# Main.net
KiCad netlist of a schematic drawn in Altium Designer
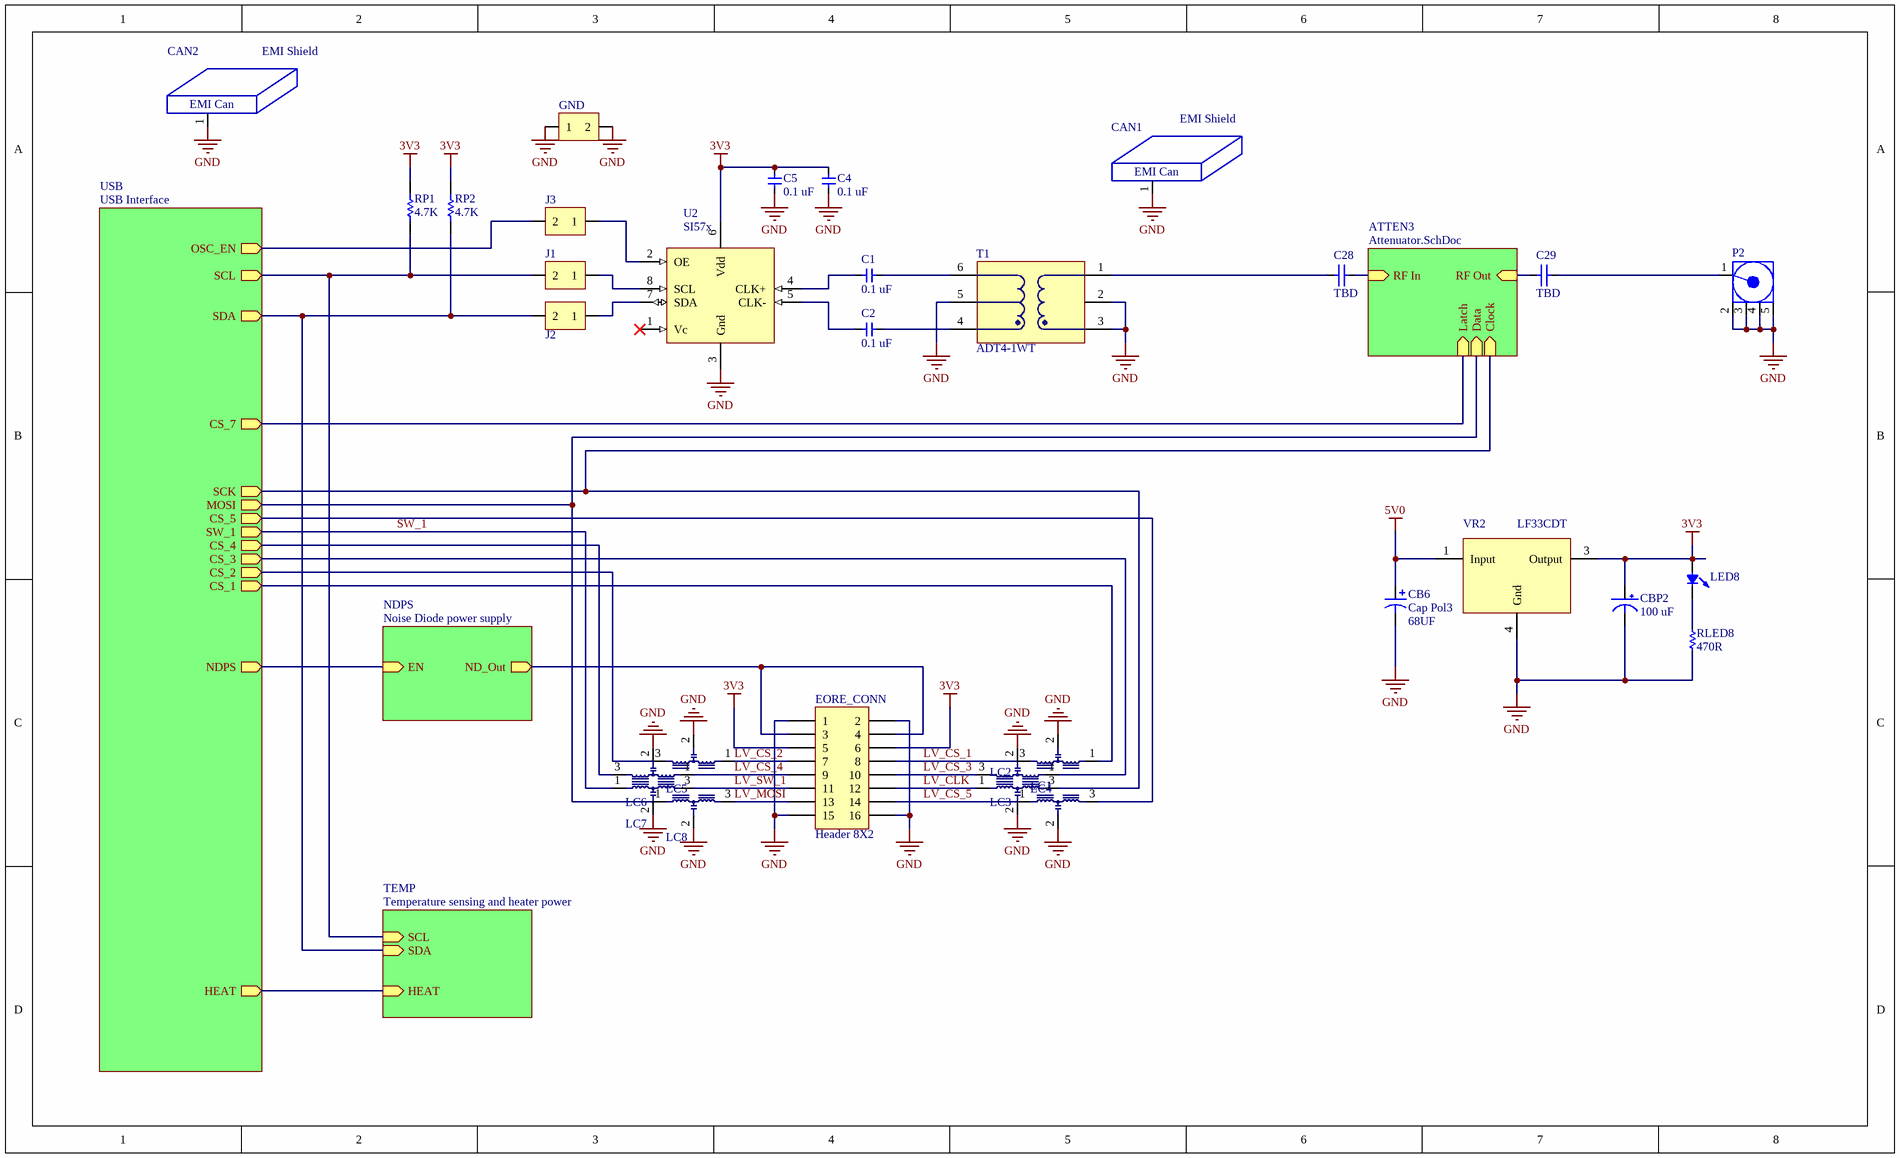
[diagram p0: Main.SchDoc]

(export (version "E")
  (design (tool "Eeschema 10.0.6"))
  (components
    (comp (ref "C1")
      (value "0.1 uF")
      (footprint "0603C")
      (description "SMT Cap")
      (fields (field (name "PUBLISHER") "Altium Limited"))
      (libsource (lib "Miscellaneous Devices") (part "Cap - SMT Small"))
    )
    (comp (ref "C2")
      (value "0.1 uF")
      (footprint "0603C")
      (description "SMT Cap")
      (fields (field (name "PUBLISHER") "Altium Limited"))
      (libsource (lib "Miscellaneous Devices") (part "Cap - SMT Small"))
    )
    (comp (ref "C4")
      (value "0.1 uF")
      (footprint "0603C")
      (description "SMT Cap")
      (fields (field (name "PUBLISHER") "Altium Limited"))
      (libsource (lib "Miscellaneous Devices") (part "Cap - SMT Small"))
    )
    (comp (ref "C5")
      (value "0.1 uF")
      (footprint "0603C")
      (description "SMT Cap")
      (fields (field (name "PUBLISHER") "Altium Limited"))
      (libsource (lib "Miscellaneous Devices") (part "Cap - SMT Small"))
    )
    (comp (ref "C28")
      (value "TBD")
      (footprint "0402C")
      (description "Capacitor")
      (fields (field (name "Comment") "Cap") (field (name "PUBLISHER") "Altium Limited"))
      (libsource (lib "Miscellaneous Devices") (part "Cap"))
    )
    (comp (ref "C29")
      (value "TBD")
      (footprint "0402C")
      (description "Capacitor")
      (fields (field (name "Comment") "Cap") (field (name "PUBLISHER") "Altium Limited"))
      (libsource (lib "Miscellaneous Devices") (part "Cap"))
    )
    (comp (ref "CAN1")
      (value "EMI Shield")
      (footprint "BMI-S-205-F")
      (description "Laird Technologies 2-part EMI can")
      (libsource (lib "RF Components") (part "BMI-S-205-F RF/EMI Can"))
    )
    (comp (ref "CAN2")
      (value "EMI Shield")
      (footprint "BMI-S-230-F-R")
      (description "Laird Technologies 2-part EMI can")
      (libsource (lib "RF Components") (part "BMI-S-230-F-R RF/EMI Can"))
    )
    (comp (ref "CB6")
      (value "Cap Pol3")
      (footprint "V")
      (description "KEMET T520 KO-CAP  Polymer SMT Tantalum")
      (fields (field (name "ALTIUM_VALUE") "68UF") (field (name "VOLTAGE") "10V"))
      (libsource (lib "Miscellaneous Devices") (part "Cap Pol3"))
    )
    (comp (ref "CBP2")
      (value "100 uF")
      (footprint "B")
      (libsource (lib "DAQ Sstem") (part "100 uf SMT Panasonic Cap"))
    )
    (comp (ref "EORE_CONN")
      (value "Header 8X2")
      (footprint "SMT 16-pin rectangular header")
      (description "Header, 8-Pin, Dual row")
      (fields (field (name "PUBLISHER") "Altium Limited"))
      (libsource (lib "Miscellaneous Connectors") (part "Header 8X2"))
    )
    (comp (ref "GND")
      (value "Jumper")
      (footprint "HDR1X2")
      (description "Jumper - 2-Pin")
      (fields (field (name "PUBLISHER") "Altium Limited"))
      (libsource (lib "") (part "Jumper - 2 Pin_1"))
    )
    (comp (ref "J1")
      (value "Jumper")
      (footprint "0603R")
      (description "Jumper - 2-Pin")
      (fields (field (name "PUBLISHER") "Altium Limited"))
      (libsource (lib "Miscellaneous Connectors") (part "Jumper - 2 Pin"))
    )
    (comp (ref "J2")
      (value "Jumper")
      (footprint "0603R")
      (description "Jumper - 2-Pin")
      (fields (field (name "PUBLISHER") "Altium Limited"))
      (libsource (lib "Miscellaneous Connectors") (part "Jumper - 2 Pin"))
    )
    (comp (ref "J3")
      (value "Jumper")
      (footprint "0603R")
      (description "Jumper - 2-Pin")
      (fields (field (name "PUBLISHER") "Altium Limited"))
      (libsource (lib "Miscellaneous Connectors") (part "Jumper - 2 Pin"))
    )
    (comp (ref "LC1")
      (value "MEM2012F")
      (footprint "MEM2012S LC Filter")
      (description "Signal Line 3-terminal Filters")
      (libsource (lib "Unsorted") (part "MEM2012F - Signal Filter"))
    )
    (comp (ref "LC2")
      (value "MEM2012F")
      (footprint "MEM2012S LC Filter")
      (description "Signal Line 3-terminal Filters")
      (libsource (lib "Unsorted") (part "MEM2012F - Signal Filter"))
    )
    (comp (ref "LC3")
      (value "MEM2012F")
      (footprint "MEM2012S LC Filter")
      (description "Signal Line 3-terminal Filters")
      (libsource (lib "Unsorted") (part "MEM2012F - Signal Filter"))
    )
    (comp (ref "LC4")
      (value "MEM2012F")
      (footprint "MEM2012S LC Filter")
      (description "Signal Line 3-terminal Filters")
      (libsource (lib "Unsorted") (part "MEM2012F - Signal Filter"))
    )
    (comp (ref "LC5")
      (value "MEM2012F")
      (footprint "MEM2012S LC Filter")
      (description "Signal Line 3-terminal Filters")
      (libsource (lib "Unsorted") (part "MEM2012F - Signal Filter"))
    )
    (comp (ref "LC6")
      (value "MEM2012F")
      (footprint "MEM2012S LC Filter")
      (description "Signal Line 3-terminal Filters")
      (libsource (lib "Unsorted") (part "MEM2012F - Signal Filter"))
    )
    (comp (ref "LC7")
      (value "MEM2012F")
      (footprint "MEM2012S LC Filter")
      (description "Signal Line 3-terminal Filters")
      (libsource (lib "Unsorted") (part "MEM2012F - Signal Filter"))
    )
    (comp (ref "LC8")
      (value "MEM2012F")
      (footprint "MEM2012S LC Filter")
      (description "Signal Line 3-terminal Filters")
      (libsource (lib "Unsorted") (part "MEM2012F - Signal Filter"))
    )
    (comp (ref "LED8")
      (value "LED0")
      (footprint "T1 LED")
      (description "T 1 3/4 LED")
      (fields (field (name "PUBLISHER") "Altium Limited"))
      (libsource (lib "Miscellaneous Devices") (part "LED0"))
    )
    (comp (ref "P2")
      (value "COAX-M")
      (footprint "SMA Jack - PCB Edge - MultiSize")
      (description "RF Coaxial PCB Connector, MMCX; Thru-Hole, Vertical Mount Plug,  50 Ohm Impedance")
      (fields (field (name "PUBLISHER") "Altium Limited"))
      (libsource (lib "Miscellaneous Connectors") (part "COAX-M"))
    )
    (comp (ref "RLED8")
      (value "470R")
      (footprint "0603R")
      (description "Semiconductor Resistor")
      (fields (field (name "Comment") "Res Semi Small") (field (name "PUBLISHER") "Altium Limited"))
      (libsource (lib "Miscellaneous Devices") (part "Res Semi Small"))
    )
    (comp (ref "RP1")
      (value "4.7K")
      (footprint "0603R")
      (description "Semiconductor Resistor")
      (fields (field (name "Comment") "Res Semi") (field (name "PUBLISHER") "Altium Limited"))
      (libsource (lib "Miscellaneous Devices") (part "Res Semi"))
    )
    (comp (ref "RP2")
      (value "4.7K")
      (footprint "0603R")
      (description "Semiconductor Resistor")
      (fields (field (name "Comment") "Res Semi") (field (name "PUBLISHER") "Altium Limited"))
      (libsource (lib "Miscellaneous Devices") (part "Res Semi"))
    )
    (comp (ref "T1")
      (value "ADT4-1WT")
      (footprint "CD542")
      (description "Surface Mount RF Transformer")
      (libsource (lib "RF Components") (part "ADT4-1WT"))
    )
    (comp (ref "U2")
      (value "SI57x")
      (footprint "SI57x")
      (description "10 MHZ TO 1.4 GHZ I2C PROGRAMMABLE XO/VCXO")
      (libsource (lib "RF Components") (part "SI570"))
    )
    (comp (ref "VR2")
      (value "LF33CDT")
      (footprint "TO228P1000-3_4N")
      (description "Very low drop 500 ma voltage regulators")
      (libsource (lib "DAQ System") (part "LF33CDT"))
    )
  )
  (nets
    (net (code "1") (name "/CS_1") (class "Default")
      (node (ref "LC4") (pin "1") (pinfunction "1_1") (pintype "passive"))
    )
    (net (code "2") (name "/CS_2") (class "Default")
      (node (ref "LC5") (pin "3") (pinfunction "3_3") (pintype "passive"))
    )
    (net (code "3") (name "/CS_3") (class "Default")
      (node (ref "LC3") (pin "1") (pinfunction "1_1") (pintype "passive"))
    )
    (net (code "4") (name "/CS_4") (class "Default")
      (node (ref "LC6") (pin "3") (pinfunction "3_3") (pintype "passive"))
    )
    (net (code "5") (name "/CS_5") (class "Default")
      (node (ref "LC1") (pin "3") (pinfunction "3_3") (pintype "passive"))
    )
    (net (code "8") (name "/LV_CLK") (class "Default")
      (node (ref "EORE_CONN") (pin "12") (pinfunction "12_12") (pintype "passive"))
      (node (ref "LC2") (pin "1") (pinfunction "1_1") (pintype "passive"))
    )
    (net (code "9") (name "/LV_CS_1") (class "Default")
      (node (ref "EORE_CONN") (pin "8") (pinfunction "8_8") (pintype "passive"))
      (node (ref "LC4") (pin "3") (pinfunction "3_3") (pintype "passive"))
    )
    (net (code "10") (name "/LV_CS_2") (class "Default")
      (node (ref "EORE_CONN") (pin "7") (pinfunction "7_7") (pintype "passive"))
      (node (ref "LC5") (pin "1") (pinfunction "1_1") (pintype "passive"))
    )
    (net (code "11") (name "/LV_CS_3") (class "Default")
      (node (ref "EORE_CONN") (pin "10") (pinfunction "10_10") (pintype "passive"))
      (node (ref "LC3") (pin "3") (pinfunction "3_3") (pintype "passive"))
    )
    (net (code "12") (name "/LV_CS_4") (class "Default")
      (node (ref "EORE_CONN") (pin "9") (pinfunction "9_9") (pintype "passive"))
      (node (ref "LC6") (pin "1") (pinfunction "1_1") (pintype "passive"))
    )
    (net (code "13") (name "/LV_CS_5") (class "Default")
      (node (ref "EORE_CONN") (pin "14") (pinfunction "14_14") (pintype "passive"))
      (node (ref "LC1") (pin "1") (pinfunction "1_1") (pintype "passive"))
    )
    (net (code "14") (name "/LV_MOSI") (class "Default")
      (node (ref "EORE_CONN") (pin "13") (pinfunction "13_13") (pintype "passive"))
      (node (ref "LC8") (pin "3") (pinfunction "3_3") (pintype "passive"))
    )
    (net (code "15") (name "/LV_SW_1") (class "Default")
      (node (ref "EORE_CONN") (pin "11") (pinfunction "11_11") (pintype "passive"))
      (node (ref "LC7") (pin "3") (pinfunction "3_3") (pintype "passive"))
    )
    (net (code "16") (name "/MOSI") (class "Default")
      (node (ref "LC8") (pin "1") (pinfunction "1_1") (pintype "passive"))
    )
    (net (code "18") (name "/ND_Out") (class "Default")
      (node (ref "EORE_CONN") (pin "3") (pinfunction "3_3") (pintype "passive"))
      (node (ref "EORE_CONN") (pin "4") (pinfunction "4_4") (pintype "passive"))
    )
    (net (code "19") (name "/OSC_EN") (class "Default")
      (node (ref "J3") (pin "2") (pinfunction "2_2") (pintype "passive"))
    )
    (net (code "20") (name "/RF In") (class "Default")
      (node (ref "C28") (pin "2") (pinfunction "2_2") (pintype "passive"))
    )
    (net (code "21") (name "/RF Out") (class "Default")
      (node (ref "C29") (pin "1") (pinfunction "1_1") (pintype "passive"))
    )
    (net (code "22") (name "/SCK") (class "Default")
      (node (ref "LC2") (pin "3") (pinfunction "3_3") (pintype "passive"))
    )
    (net (code "23") (name "/SCL") (class "Default")
      (node (ref "J1") (pin "2") (pinfunction "2_2") (pintype "passive"))
      (node (ref "RP1") (pin "1") (pinfunction "1_1") (pintype "passive"))
    )
    (net (code "24") (name "/SDA") (class "Default")
      (node (ref "J2") (pin "2") (pinfunction "2_2") (pintype "passive"))
      (node (ref "RP2") (pin "1") (pinfunction "1_1") (pintype "passive"))
    )
    (net (code "25") (name "/SW_1") (class "Default")
      (node (ref "LC7") (pin "1") (pinfunction "1_1") (pintype "passive"))
    )
    (net (code "26") (name "3V3") (class "Default")
      (node (ref "C4") (pin "2") (pinfunction "2_2") (pintype "passive"))
      (node (ref "C5") (pin "2") (pinfunction "2_2") (pintype "passive"))
      (node (ref "CBP2") (pin "1") (pinfunction "1_1") (pintype "passive"))
      (node (ref "EORE_CONN") (pin "5") (pinfunction "5_5") (pintype "passive"))
      (node (ref "EORE_CONN") (pin "6") (pinfunction "6_6") (pintype "passive"))
      (node (ref "LED8") (pin "1") (pinfunction "1_1") (pintype "passive"))
      (node (ref "RP1") (pin "2") (pinfunction "2_2") (pintype "passive"))
      (node (ref "RP2") (pin "2") (pinfunction "2_2") (pintype "passive"))
      (node (ref "U2") (pin "6") (pinfunction "Vdd_6") (pintype "power_in"))
      (node (ref "VR2") (pin "3") (pinfunction "Output_3") (pintype "power_in"))
    )
    (net (code "27") (name "5V0") (class "Default")
      (node (ref "CB6") (pin "1") (pinfunction "1_1") (pintype "passive"))
      (node (ref "VR2") (pin "1") (pinfunction "Input_1") (pintype "power_in"))
    )
    (net (code "28") (name "GND") (class "Default")
      (node (ref "C4") (pin "1") (pinfunction "1_1") (pintype "passive"))
      (node (ref "C5") (pin "1") (pinfunction "1_1") (pintype "passive"))
      (node (ref "CAN1") (pin "1") (pintype "passive"))
      (node (ref "CAN2") (pin "1") (pintype "passive"))
      (node (ref "CB6") (pin "2") (pinfunction "2_2") (pintype "passive"))
      (node (ref "CBP2") (pin "2") (pinfunction "2_2") (pintype "passive"))
      (node (ref "EORE_CONN") (pin "1") (pinfunction "1_1") (pintype "passive"))
      (node (ref "EORE_CONN") (pin "15") (pinfunction "15_15") (pintype "passive"))
      (node (ref "EORE_CONN") (pin "16") (pinfunction "16_16") (pintype "passive"))
      (node (ref "EORE_CONN") (pin "2") (pinfunction "2_2") (pintype "passive"))
      (node (ref "GND") (pin "1") (pinfunction "1_1") (pintype "passive"))
      (node (ref "GND") (pin "2") (pinfunction "2_2") (pintype "passive"))
      (node (ref "LC1") (pin "2") (pinfunction "2_2") (pintype "passive"))
      (node (ref "LC2") (pin "2") (pinfunction "2_2") (pintype "passive"))
      (node (ref "LC3") (pin "2") (pinfunction "2_2") (pintype "passive"))
      (node (ref "LC4") (pin "2") (pinfunction "2_2") (pintype "passive"))
      (node (ref "LC5") (pin "2") (pinfunction "2_2") (pintype "passive"))
      (node (ref "LC6") (pin "2") (pinfunction "2_2") (pintype "passive"))
      (node (ref "LC7") (pin "2") (pinfunction "2_2") (pintype "passive"))
      (node (ref "LC8") (pin "2") (pinfunction "2_2") (pintype "passive"))
      (node (ref "P2") (pin "2") (pinfunction "GND_2") (pintype "power_in"))
      (node (ref "P2") (pin "3") (pinfunction "GND_3") (pintype "power_in"))
      (node (ref "P2") (pin "4") (pinfunction "GND_4") (pintype "power_in"))
      (node (ref "P2") (pin "5") (pinfunction "GND_5") (pintype "power_in"))
      (node (ref "RLED8") (pin "2") (pinfunction "2_2") (pintype "passive"))
      (node (ref "T1") (pin "2") (pinfunction "Gnd_2") (pintype "power_in"))
      (node (ref "T1") (pin "3") (pinfunction "Coupled_3") (pintype "passive"))
      (node (ref "T1") (pin "5") (pinfunction "Termination_5") (pintype "passive"))
      (node (ref "U2") (pin "3") (pinfunction "Gnd_3") (pintype "power_in"))
      (node (ref "VR2") (pin "4") (pinfunction "Gnd_4") (pintype "power_in"))
    )
    (net (code "29") (name "Net-(C2-Pad2)") (class "Default")
      (node (ref "C2") (pin "2") (pinfunction "2_2") (pintype "passive"))
      (node (ref "T1") (pin "4") (pinfunction "Termination_4") (pintype "passive"))
    )
    (net (code "30") (name "Net-(LED8-Pad2)") (class "Default")
      (node (ref "LED8") (pin "2") (pinfunction "2_2") (pintype "passive"))
      (node (ref "RLED8") (pin "1") (pinfunction "1_1") (pintype "passive"))
    )
    (net (code "31") (name "Net-(P2-Signal)") (class "Default")
      (node (ref "C29") (pin "2") (pinfunction "2_2") (pintype "passive"))
      (node (ref "P2") (pin "1") (pinfunction "Signal_1") (pintype "passive"))
    )
    (net (code "32") (name "Net-(T1-Input)") (class "Default")
      (node (ref "C28") (pin "1") (pinfunction "1_1") (pintype "passive"))
      (node (ref "T1") (pin "1") (pinfunction "Input_1") (pintype "passive"))
    )
    (net (code "33") (name "Net-(T1-Output)") (class "Default")
      (node (ref "C1") (pin "2") (pinfunction "2_2") (pintype "passive"))
      (node (ref "T1") (pin "6") (pinfunction "Output_6") (pintype "passive"))
    )
    (net (code "34") (name "Net-(U2-CLK+)") (class "Default")
      (node (ref "C1") (pin "1") (pinfunction "1_1") (pintype "passive"))
      (node (ref "U2") (pin "4") (pinfunction "CLK+_4") (pintype "input"))
    )
    (net (code "35") (name "Net-(U2-CLK-)") (class "Default")
      (node (ref "C2") (pin "1") (pinfunction "1_1") (pintype "passive"))
      (node (ref "U2") (pin "5") (pinfunction "CLK-_5") (pintype "input"))
    )
    (net (code "36") (name "Net-(U2-OE)") (class "Default")
      (node (ref "J3") (pin "1") (pinfunction "1_1") (pintype "passive"))
      (node (ref "U2") (pin "2") (pinfunction "OE_2") (pintype "input"))
    )
    (net (code "37") (name "Net-(U2-SCL)") (class "Default")
      (node (ref "J1") (pin "1") (pinfunction "1_1") (pintype "passive"))
      (node (ref "U2") (pin "8") (pinfunction "SCL_8") (pintype "input"))
    )
    (net (code "38") (name "Net-(U2-SDA)") (class "Default")
      (node (ref "J2") (pin "1") (pinfunction "1_1") (pintype "passive"))
      (node (ref "U2") (pin "7") (pinfunction "SDA_7") (pintype "bidirectional"))
    )
    (net (code "39") (name "unconnected-(U2-Vc-Pad1)") (class "Default")
      (node (ref "U2") (pin "1") (pinfunction "Vc_1") (pintype "input+no_connect"))
    )
  )
)
